# Sheet1.net
KiCad netlist of a schematic drawn in Altium Designer
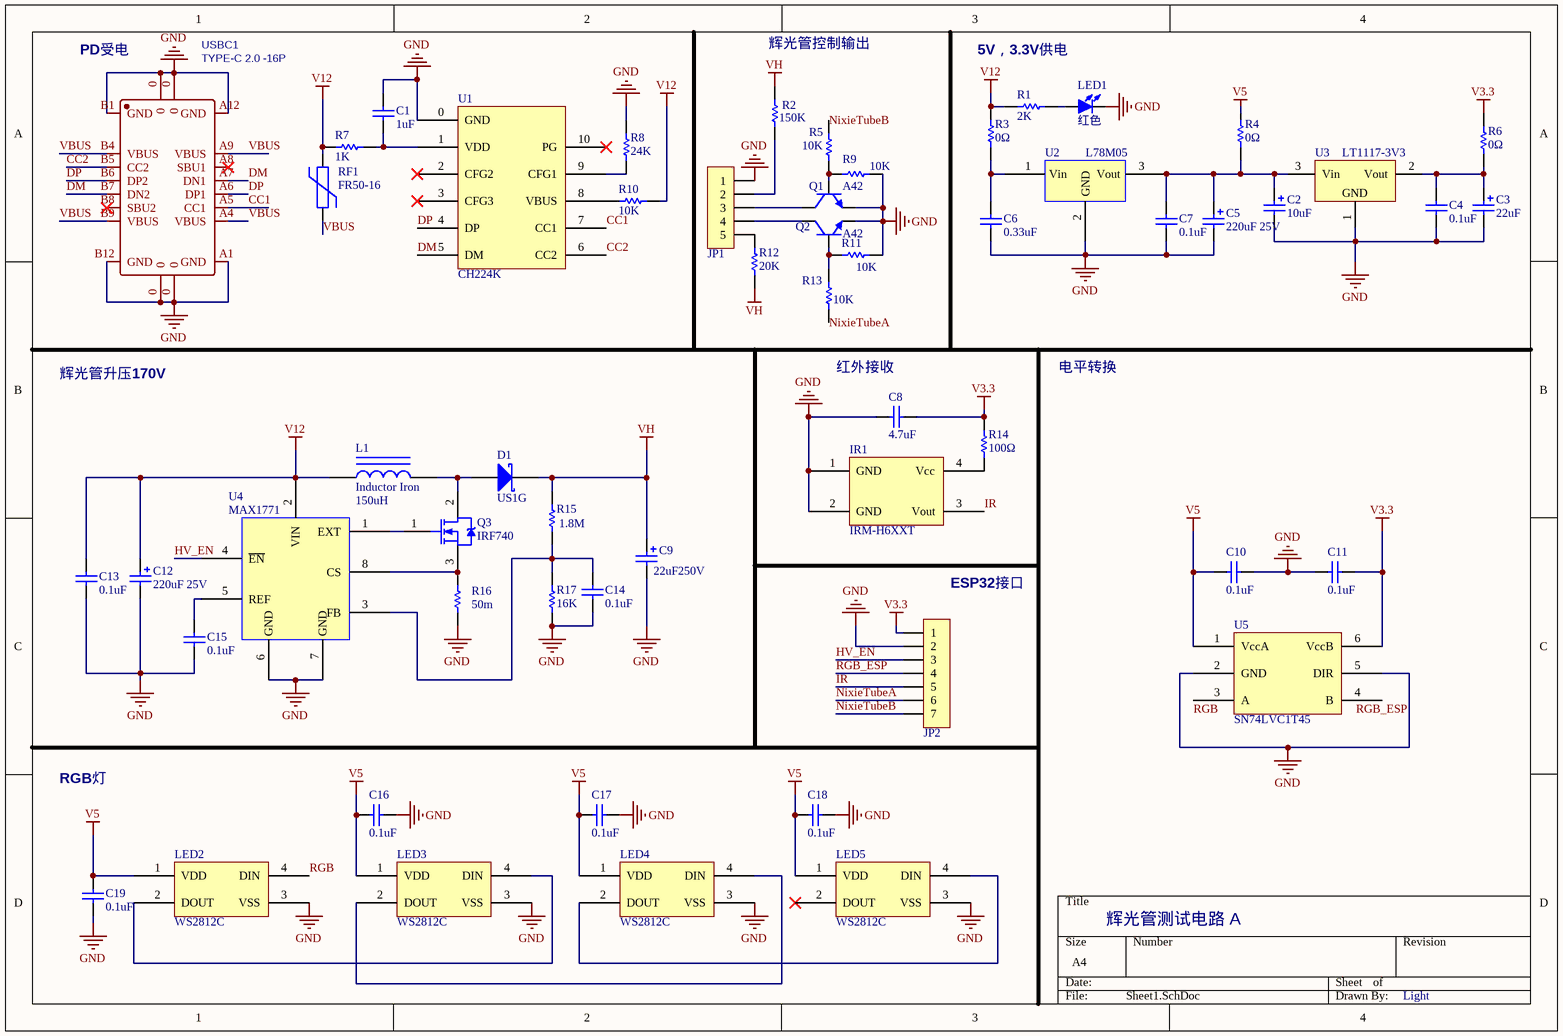
[diagram p0: Sheet1.SchDoc]

(export (version "E")
  (design (tool "Eeschema 10.0.6"))
  (components
    (comp (ref "C1")
      (value "1uF")
      (footprint "C 0805_L")
      (description "Capacitor")
      (fields (field (name "Comment") "Cap") (field (name "PUBLISHER") "Altium Limited"))
      (libsource (lib "Nixie") (part "Cap"))
    )
    (comp (ref "C2")
      (value "10uF")
      (footprint "CM B(4*5.4)")
      (description "Polarized Capacitor (Radial)")
      (fields (field (name "Comment") "Cap Pol1") (field (name "PUBLISHER") "Altium Limited"))
      (libsource (lib "Nixie") (part "Cap Pol1"))
    )
    (comp (ref "C3")
      (value "22uF")
      (footprint "CD C(6032)")
      (description "Polarized Capacitor (Radial)")
      (fields (field (name "Comment") "Cap Pol1") (field (name "PUBLISHER") "Altium Limited"))
      (libsource (lib "Nixie") (part "Cap Pol1"))
    )
    (comp (ref "C4")
      (value "0.1uF")
      (footprint "C 0805_L")
      (description "Capacitor")
      (fields (field (name "Comment") "Cap") (field (name "PUBLISHER") "Altium Limited"))
      (libsource (lib "Nixie") (part "Cap"))
    )
    (comp (ref "C5")
      (value "220uF 25V")
      (footprint "CM E(8*10.2)")
      (description "Polarized Capacitor (Radial)")
      (fields
        (field (name "VOLTAGE") "16V")
        (field (name "Comment") "Cap Pol1")
        (field (name "PUBLISHER") "Altium Limited")
      )
      (libsource (lib "Nixie") (part "Cap Pol1_2"))
    )
    (comp (ref "C6")
      (value "0.33uF")
      (footprint "C 0805_L")
      (description "Capacitor")
      (fields (field (name "Comment") "Cap") (field (name "PUBLISHER") "Altium Limited"))
      (libsource (lib "Nixie") (part "Cap"))
    )
    (comp (ref "C7")
      (value "0.1uF")
      (footprint "C 0805_L")
      (description "Capacitor")
      (fields (field (name "Comment") "Cap") (field (name "PUBLISHER") "Altium Limited"))
      (libsource (lib "Nixie") (part "Cap"))
    )
    (comp (ref "C8")
      (value "4.7uF")
      (footprint "C 0805_L")
      (description "Capacitor")
      (fields (field (name "Comment") "Cap") (field (name "PUBLISHER") "Altium Limited"))
      (libsource (lib "Nixie") (part "Cap"))
    )
    (comp (ref "C9")
      (value "22uF250V")
      (footprint "CAP 5.0*10*16-H - GD")
      (description "Polarized Capacitor (Radial)")
      (fields (field (name "Comment") "Cap Pol1") (field (name "PUBLISHER") "Altium Limited"))
      (libsource (lib "Nixie") (part "Cap Pol1_3"))
    )
    (comp (ref "C10")
      (value "0.1uF")
      (footprint "C 0805_L")
      (description "Capacitor")
      (fields (field (name "Comment") "Cap") (field (name "PUBLISHER") "Altium Limited"))
      (libsource (lib "Nixie") (part "Cap"))
    )
    (comp (ref "C11")
      (value "0.1uF")
      (footprint "C 0805_L")
      (description "Capacitor")
      (fields (field (name "Comment") "Cap") (field (name "PUBLISHER") "Altium Limited"))
      (libsource (lib "Nixie") (part "Cap"))
    )
    (comp (ref "C12")
      (value "220uF 25V")
      (footprint "CM E(8*10.2)")
      (description "Polarized Capacitor (Radial)")
      (fields
        (field (name "VOLTAGE") "16V")
        (field (name "Comment") "Cap Pol1")
        (field (name "PUBLISHER") "Altium Limited")
      )
      (libsource (lib "Nixie") (part "Cap Pol1_2"))
    )
    (comp (ref "C13")
      (value "0.1uF")
      (footprint "C 0805_L")
      (description "Capacitor")
      (fields (field (name "Comment") "Cap") (field (name "PUBLISHER") "Altium Limited"))
      (libsource (lib "Nixie") (part "Cap"))
    )
    (comp (ref "C14")
      (value "0.1uF")
      (footprint "C 0805_L")
      (description "Capacitor")
      (fields (field (name "Comment") "Cap") (field (name "PUBLISHER") "Altium Limited"))
      (libsource (lib "Nixie") (part "Cap"))
    )
    (comp (ref "C15")
      (value "0.1uF")
      (footprint "C 0805_L")
      (description "Capacitor")
      (fields (field (name "Comment") "Cap") (field (name "PUBLISHER") "Altium Limited"))
      (libsource (lib "Schlib1") (part "Cap"))
    )
    (comp (ref "C16")
      (value "0.1uF")
      (footprint "C 0805_L")
      (description "Capacitor")
      (fields (field (name "Comment") "Cap") (field (name "PUBLISHER") "Altium Limited"))
      (libsource (lib "Nixie") (part "Cap"))
    )
    (comp (ref "C17")
      (value "0.1uF")
      (footprint "C 0805_L")
      (description "Capacitor")
      (fields (field (name "Comment") "Cap") (field (name "PUBLISHER") "Altium Limited"))
      (libsource (lib "Nixie") (part "Cap"))
    )
    (comp (ref "C18")
      (value "0.1uF")
      (footprint "C 0805_L")
      (description "Capacitor")
      (fields (field (name "Comment") "Cap") (field (name "PUBLISHER") "Altium Limited"))
      (libsource (lib "Nixie") (part "Cap"))
    )
    (comp (ref "C19")
      (value "0.1uF")
      (footprint "C 0805_L")
      (description "Capacitor")
      (fields (field (name "Comment") "Cap") (field (name "PUBLISHER") "Altium Limited"))
      (libsource (lib "Nixie") (part "Cap"))
    )
    (comp (ref "D1")
      (value "US1G")
      (footprint "SMA")
      (description "Schottky Diode")
      (fields (field (name "PUBLISHER") "Altium Limited"))
      (libsource (lib "Nixie") (part "D Schottky"))
    )
    (comp (ref "IR1") (value "IRM-H6XXT") (footprint "SMD4_IR") (libsource (lib "Nixie") (part "IR")))
    (comp (ref "JP1")
      (value "HDR-1X5")
      (footprint "XH2.54-LI-5P")
      (description "5P接插件")
      (fields (field (name "版权归属") "封装库来自淘宝 ID：黄晶宝石"))
      (libsource (lib "Nixie") (part "Header 5"))
    )
    (comp (ref "JP2")
      (value "HDR-1X7")
      (footprint "HDR2.54-LI-7P")
      (description "7P接插件")
      (fields (field (name "版权归属") "封装库来自淘宝 ID：黄晶宝石"))
      (libsource (lib "Nixie") (part "Header 7"))
    )
    (comp (ref "L1")
      (value "Inductor Iron")
      (footprint "CDRH127")
      (description "Magnetic-Core Inductor")
      (fields (field (name "ALTIUM_VALUE") "150uH") (field (name "PUBLISHER") "Altium Limited"))
      (libsource (lib "Nixie") (part "Inductor Iron"))
    )
    (comp (ref "LED1")
      (value "红色")
      (footprint "LED 1206R")
      (description "贴片LED")
      (fields (field (name "版权归属") "封装库来自淘宝 ID：黄晶宝石"))
      (libsource (lib "Nixie") (part "LED-SMD"))
    )
    (comp (ref "LED2")
      (value "WS2812C")
      (footprint "WS2812")
      (description "RGB发光管")
      (libsource (lib "Nixie") (part "WS2812"))
    )
    (comp (ref "LED3")
      (value "WS2812C")
      (footprint "WS2812")
      (description "RGB发光管")
      (libsource (lib "Nixie") (part "WS2812"))
    )
    (comp (ref "LED4")
      (value "WS2812C")
      (footprint "WS2812")
      (description "RGB发光管")
      (libsource (lib "Nixie") (part "WS2812"))
    )
    (comp (ref "LED5")
      (value "WS2812C")
      (footprint "WS2812")
      (description "RGB发光管")
      (libsource (lib "Nixie") (part "WS2812"))
    )
    (comp (ref "Q1")
      (value "A42")
      (footprint "SOT23-3L")
      (description "NPN三极管")
      (fields (field (name "PUBLISHER") "Altium Limited"))
      (libsource (lib "Nixie") (part "BCP68"))
    )
    (comp (ref "Q2")
      (value "A42")
      (footprint "SOT23-3L")
      (description "NPN三极管")
      (fields (field (name "PUBLISHER") "Altium Limited"))
      (libsource (lib "Nixie") (part "BCP68"))
    )
    (comp (ref "Q3")
      (value "IRF740")
      (footprint "TO-263-2L")
      (description "N-Channel Power MOSFET")
      (fields (field (name "PUBLISHER") "Altium Limited"))
      (libsource (lib "Nixie") (part "NMOS-2"))
    )
    (comp (ref "R1")
      (value "2K")
      (footprint "R 0805_L")
      (description "Resistor")
      (fields (field (name "PUBLISHER") "Altium Limited"))
      (libsource (lib "Nixie") (part "Resistor"))
    )
    (comp (ref "R2")
      (value "150K")
      (footprint "R 0805_L")
      (description "Semiconductor Resistor")
      (fields (field (name "Comment") "Res Semi") (field (name "PUBLISHER") "Altium Limited"))
      (libsource (lib "Schlib1") (part "Res"))
    )
    (comp (ref "R3")
      (value "0Ω")
      (footprint "R 0805_L")
      (description "Resistor")
      (fields (field (name "PUBLISHER") "Altium Limited"))
      (libsource (lib "Nixie") (part "Resistor"))
    )
    (comp (ref "R4")
      (value "0Ω")
      (footprint "R 0805_L")
      (description "Resistor")
      (fields (field (name "PUBLISHER") "Altium Limited"))
      (libsource (lib "Nixie") (part "Resistor"))
    )
    (comp (ref "R5")
      (value "10K")
      (footprint "R 0805_L")
      (description "Resistor")
      (fields (field (name "PUBLISHER") "Altium Limited"))
      (libsource (lib "Nixie") (part "Resistor"))
    )
    (comp (ref "R6")
      (value "0Ω")
      (footprint "R 0805_L")
      (description "Resistor")
      (fields (field (name "PUBLISHER") "Altium Limited"))
      (libsource (lib "Nixie") (part "Resistor"))
    )
    (comp (ref "R7")
      (value "1K")
      (footprint "R 1206_L")
      (description "Resistor")
      (fields (field (name "PUBLISHER") "Altium Limited"))
      (libsource (lib "Nixie") (part "Resistor"))
    )
    (comp (ref "R8")
      (value "24K")
      (footprint "R 0805_L")
      (description "Resistor")
      (fields (field (name "PUBLISHER") "Altium Limited"))
      (libsource (lib "Nixie") (part "Resistor"))
    )
    (comp (ref "R9")
      (value "10K")
      (footprint "R 0805_L")
      (description "Resistor")
      (fields (field (name "PUBLISHER") "Altium Limited"))
      (libsource (lib "Nixie") (part "Resistor"))
    )
    (comp (ref "R10")
      (value "10K")
      (footprint "R 0805_L")
      (description "Resistor")
      (fields (field (name "PUBLISHER") "Altium Limited"))
      (libsource (lib "Nixie") (part "Resistor"))
    )
    (comp (ref "R11")
      (value "10K")
      (footprint "R 0805_L")
      (description "Resistor")
      (fields (field (name "PUBLISHER") "Altium Limited"))
      (libsource (lib "Nixie") (part "Resistor"))
    )
    (comp (ref "R12")
      (value "20K")
      (footprint "R 0805_L")
      (description "Semiconductor Resistor")
      (fields (field (name "Comment") "Res Semi") (field (name "PUBLISHER") "Altium Limited"))
      (libsource (lib "Schlib1") (part "Res"))
    )
    (comp (ref "R13")
      (value "10K")
      (footprint "R 0805_L")
      (description "Resistor")
      (fields (field (name "PUBLISHER") "Altium Limited"))
      (libsource (lib "Nixie") (part "Resistor"))
    )
    (comp (ref "R14")
      (value "100Ω")
      (footprint "R 0805_L")
      (description "Resistor")
      (fields (field (name "PUBLISHER") "Altium Limited"))
      (libsource (lib "Nixie") (part "Resistor"))
    )
    (comp (ref "R15")
      (value "1.8M")
      (footprint "R 0805_L")
      (description "Semiconductor Resistor")
      (fields (field (name "Comment") "Res Semi") (field (name "PUBLISHER") "Altium Limited"))
      (libsource (lib "Nixie") (part "Res Semi"))
    )
    (comp (ref "R16")
      (value "50m")
      (footprint "R 1206_L")
      (description "Semiconductor Resistor")
      (fields (field (name "Comment") "Res Semi") (field (name "PUBLISHER") "Altium Limited"))
      (libsource (lib "Nixie") (part "Res Semi"))
    )
    (comp (ref "R17")
      (value "16K")
      (footprint "R 0805_L")
      (description "Resistor")
      (fields (field (name "PUBLISHER") "Altium Limited"))
      (libsource (lib "Nixie") (part "Resistor"))
    )
    (comp (ref "RF1")
      (value "FR50-16")
      (footprint "FU 1206")
      (description "PPTC自恢复保险丝")
      (fields (field (name "版权归属") "封装库来自淘宝卖家 ID：黄晶宝石"))
      (libsource (lib "Nixie") (part "PPTC"))
    )
    (comp (ref "U1")
      (value "CH224K")
      (footprint "ESSOP10")
      (description "PD协议受电芯片")
      (libsource (lib "Nixie") (part "CH224K"))
    )
    (comp (ref "U2") (value "L78M05") (footprint "TO-252") (libsource (lib "Nixie") (part "L78M05")))
    (comp (ref "U3")
      (value "LT1117-3V3")
      (footprint "SOT223_L")
      (description "三端稳压芯片")
      (fields (field (name "版权归属") "源创客"))
      (libsource (lib "Nixie") (part "AMS1117"))
    )
    (comp (ref "U4") (value "MAX1771") (footprint "SOIC8") (libsource (lib "Nixie") (part "MAX1771")))
    (comp (ref "U5")
      (value "SN74LVC1T45")
      (footprint "SOT23-6L")
      (description "单路逻辑电平转换")
      (libsource (lib "Nixie") (part "SN74LVC1T45"))
    )
    (comp (ref "USBC1")
      (value "TYPE-C 2.0 -16P")
      (footprint "USB-C-SMD_TYPE-C-USB-5")
      (description "USB2.0 Type-C 母座 16Pin")
      (libsource (lib "Nixie") (part "USB2.0 Type-C 16Pin母座"))
    )
  )
  (nets
    (net (code "1") (name "/CC1") (class "Default")
      (node (ref "U1") (pin "7") (pinfunction "CC1_7") (pintype "passive"))
      (node (ref "USBC1") (pin "A5") (pinfunction "CC1_A5") (pintype "passive"))
    )
    (net (code "2") (name "/CC2") (class "Default")
      (node (ref "U1") (pin "6") (pinfunction "CC2_6") (pintype "passive"))
      (node (ref "USBC1") (pin "B5") (pinfunction "CC2_B5") (pintype "passive"))
    )
    (net (code "3") (name "/DM") (class "Default")
      (node (ref "U1") (pin "5") (pinfunction "DM_5") (pintype "passive"))
      (node (ref "USBC1") (pin "A7") (pinfunction "DN1_A7") (pintype "passive"))
      (node (ref "USBC1") (pin "B7") (pinfunction "DN2_B7") (pintype "passive"))
    )
    (net (code "4") (name "/DP") (class "Default")
      (node (ref "U1") (pin "4") (pinfunction "DP_4") (pintype "passive"))
      (node (ref "USBC1") (pin "A6") (pinfunction "DP1_A6") (pintype "passive"))
      (node (ref "USBC1") (pin "B6") (pinfunction "DP2_B6") (pintype "passive"))
    )
    (net (code "5") (name "/HV_EN") (class "Default")
      (node (ref "JP2") (pin "3") (pinfunction "3_3") (pintype "passive"))
      (node (ref "U4") (pin "4") (pinfunction "~{EN}_4") (pintype "passive"))
    )
    (net (code "6") (name "/IR") (class "Default")
      (node (ref "IR1") (pin "3") (pinfunction "Vout_3") (pintype "passive"))
      (node (ref "JP2") (pin "5") (pinfunction "5_5") (pintype "passive"))
    )
    (net (code "7") (name "/NixieTubeA") (class "Default")
      (node (ref "JP2") (pin "6") (pinfunction "6_6") (pintype "passive"))
      (node (ref "R13") (pin "2") (pinfunction "2_2") (pintype "passive"))
    )
    (net (code "8") (name "/NixieTubeB") (class "Default")
      (node (ref "JP2") (pin "7") (pinfunction "7_7") (pintype "passive"))
      (node (ref "R5") (pin "2") (pinfunction "2_2") (pintype "passive"))
    )
    (net (code "9") (name "/RGB") (class "Default")
      (node (ref "LED2") (pin "4") (pinfunction "DIN_4") (pintype "passive"))
      (node (ref "U5") (pin "3") (pinfunction "A_3") (pintype "passive"))
    )
    (net (code "10") (name "/RGB_ESP") (class "Default")
      (node (ref "JP2") (pin "4") (pinfunction "4_4") (pintype "passive"))
      (node (ref "U5") (pin "4") (pinfunction "B_4") (pintype "passive"))
    )
    (net (code "11") (name "/VBUS") (class "Default")
      (node (ref "RF1") (pin "1") (pinfunction "1_1") (pintype "passive"))
      (node (ref "USBC1") (pin "A4") (pinfunction "VBUS_A4") (pintype "passive"))
      (node (ref "USBC1") (pin "A9") (pinfunction "VBUS_A9") (pintype "passive"))
      (node (ref "USBC1") (pin "B4") (pinfunction "VBUS_B4") (pintype "passive"))
      (node (ref "USBC1") (pin "B9") (pinfunction "VBUS_B9") (pintype "passive"))
    )
    (net (code "12") (name "GND") (class "Default")
      (node (ref "C1") (pin "2") (pinfunction "2_2") (pintype "passive"))
      (node (ref "C10") (pin "1") (pinfunction "1_1") (pintype "passive"))
      (node (ref "C11") (pin "2") (pinfunction "2_2") (pintype "passive"))
      (node (ref "C12") (pin "2") (pinfunction "2_2") (pintype "passive"))
      (node (ref "C13") (pin "1") (pinfunction "1_1") (pintype "passive"))
      (node (ref "C14") (pin "1") (pinfunction "1_1") (pintype "passive"))
      (node (ref "C15") (pin "2") (pinfunction "2_2") (pintype "passive"))
      (node (ref "C16") (pin "1") (pinfunction "1_1") (pintype "passive"))
      (node (ref "C17") (pin "1") (pinfunction "1_1") (pintype "passive"))
      (node (ref "C18") (pin "1") (pinfunction "1_1") (pintype "passive"))
      (node (ref "C19") (pin "1") (pinfunction "1_1") (pintype "passive"))
      (node (ref "C2") (pin "2") (pinfunction "2_2") (pintype "passive"))
      (node (ref "C3") (pin "2") (pinfunction "2_2") (pintype "passive"))
      (node (ref "C4") (pin "1") (pinfunction "1_1") (pintype "passive"))
      (node (ref "C5") (pin "2") (pinfunction "2_2") (pintype "passive"))
      (node (ref "C6") (pin "1") (pinfunction "1_1") (pintype "passive"))
      (node (ref "C7") (pin "1") (pinfunction "1_1") (pintype "passive"))
      (node (ref "C8") (pin "2") (pinfunction "2_2") (pintype "passive"))
      (node (ref "C9") (pin "2") (pinfunction "2_2") (pintype "passive"))
      (node (ref "IR1") (pin "1") (pinfunction "GND_1") (pintype "passive"))
      (node (ref "IR1") (pin "2") (pinfunction "GND_2") (pintype "passive"))
      (node (ref "JP1") (pin "1") (pinfunction "1_1") (pintype "passive"))
      (node (ref "JP2") (pin "2") (pinfunction "2_2") (pintype "passive"))
      (node (ref "LED1") (pin "2") (pinfunction "K_2") (pintype "passive"))
      (node (ref "LED2") (pin "3") (pinfunction "VSS_3") (pintype "passive"))
      (node (ref "LED3") (pin "3") (pinfunction "VSS_3") (pintype "passive"))
      (node (ref "LED4") (pin "3") (pinfunction "VSS_3") (pintype "passive"))
      (node (ref "LED5") (pin "3") (pinfunction "VSS_3") (pintype "passive"))
      (node (ref "Q1") (pin "2") (pinfunction "E_2") (pintype "passive"))
      (node (ref "Q2") (pin "2") (pinfunction "E_2") (pintype "passive"))
      (node (ref "R11") (pin "2") (pinfunction "2_2") (pintype "passive"))
      (node (ref "R16") (pin "2") (pinfunction "2_2") (pintype "passive"))
      (node (ref "R17") (pin "1") (pinfunction "1_1") (pintype "passive"))
      (node (ref "R8") (pin "1") (pinfunction "1_1") (pintype "passive"))
      (node (ref "R9") (pin "2") (pinfunction "2_2") (pintype "passive"))
      (node (ref "U1") (pin "0") (pinfunction "GND_0") (pintype "passive"))
      (node (ref "U2") (pin "2") (pinfunction "GND_2") (pintype "passive"))
      (node (ref "U3") (pin "1") (pinfunction "GND_1") (pintype "passive"))
      (node (ref "U4") (pin "6") (pinfunction "GND_6") (pintype "passive"))
      (node (ref "U4") (pin "7") (pinfunction "GND_7") (pintype "passive"))
      (node (ref "U5") (pin "2") (pinfunction "GND_2") (pintype "passive"))
      (node (ref "U5") (pin "5") (pinfunction "DIR_5") (pintype "passive"))
      (node (ref "USBC1") (pin "0") (pinfunction "0_0") (pintype "passive"))
      (node (ref "USBC1") (pin "A1") (pinfunction "GND_A1") (pintype "passive"))
      (node (ref "USBC1") (pin "A12") (pinfunction "GND_A12") (pintype "passive"))
      (node (ref "USBC1") (pin "B1") (pinfunction "GND_B1") (pintype "passive"))
      (node (ref "USBC1") (pin "B12") (pinfunction "GND_B12") (pintype "passive"))
    )
    (net (code "13") (name "Net-(D1-A)") (class "Default")
      (node (ref "D1") (pin "1") (pinfunction "A_1") (pintype "passive"))
      (node (ref "L1") (pin "2") (pinfunction "2_2") (pintype "passive"))
      (node (ref "Q3") (pin "2") (pinfunction "D_2") (pintype "passive"))
    )
    (net (code "14") (name "Net-(IR1-Vcc)") (class "Default")
      (node (ref "IR1") (pin "4") (pinfunction "Vcc_4") (pintype "passive"))
      (node (ref "R14") (pin "1") (pinfunction "1_1") (pintype "passive"))
    )
    (net (code "15") (name "Net-(JP1-Pad2)") (class "Default")
      (node (ref "JP1") (pin "2") (pinfunction "2_2") (pintype "passive"))
      (node (ref "R2") (pin "1") (pinfunction "1_1") (pintype "passive"))
    )
    (net (code "16") (name "Net-(JP1-Pad5)") (class "Default")
      (node (ref "JP1") (pin "5") (pinfunction "5_5") (pintype "passive"))
      (node (ref "R12") (pin "2") (pinfunction "2_2") (pintype "passive"))
    )
    (net (code "17") (name "Net-(LED1-A)") (class "Default")
      (node (ref "LED1") (pin "1") (pinfunction "A_1") (pintype "passive"))
      (node (ref "R1") (pin "1") (pinfunction "1_1") (pintype "passive"))
    )
    (net (code "18") (name "Net-(LED2-DOUT)") (class "Default")
      (node (ref "LED2") (pin "2") (pinfunction "DOUT_2") (pintype "passive"))
      (node (ref "LED3") (pin "4") (pinfunction "DIN_4") (pintype "passive"))
    )
    (net (code "19") (name "Net-(LED3-DOUT)") (class "Default")
      (node (ref "LED3") (pin "2") (pinfunction "DOUT_2") (pintype "passive"))
      (node (ref "LED4") (pin "4") (pinfunction "DIN_4") (pintype "passive"))
    )
    (net (code "20") (name "Net-(LED4-DOUT)") (class "Default")
      (node (ref "LED4") (pin "2") (pinfunction "DOUT_2") (pintype "passive"))
      (node (ref "LED5") (pin "4") (pinfunction "DIN_4") (pintype "passive"))
    )
    (net (code "21") (name "Net-(Q1-B)") (class "Default")
      (node (ref "Q1") (pin "1") (pinfunction "B_1") (pintype "passive"))
      (node (ref "R5") (pin "1") (pinfunction "1_1") (pintype "passive"))
      (node (ref "R9") (pin "1") (pinfunction "1_1") (pintype "passive"))
    )
    (net (code "22") (name "Net-(Q1-C)") (class "Default")
      (node (ref "JP1") (pin "3") (pinfunction "3_3") (pintype "passive"))
      (node (ref "Q1") (pin "3") (pinfunction "C_3") (pintype "passive"))
    )
    (net (code "23") (name "Net-(Q2-B)") (class "Default")
      (node (ref "Q2") (pin "1") (pinfunction "B_1") (pintype "passive"))
      (node (ref "R11") (pin "1") (pinfunction "1_1") (pintype "passive"))
      (node (ref "R13") (pin "1") (pinfunction "1_1") (pintype "passive"))
    )
    (net (code "24") (name "Net-(Q2-C)") (class "Default")
      (node (ref "JP1") (pin "4") (pinfunction "4_4") (pintype "passive"))
      (node (ref "Q2") (pin "3") (pinfunction "C_3") (pintype "passive"))
    )
    (net (code "25") (name "Net-(Q3-G)") (class "Default")
      (node (ref "Q3") (pin "1") (pinfunction "G_1") (pintype "passive"))
      (node (ref "U4") (pin "1") (pinfunction "EXT_1") (pintype "passive"))
    )
    (net (code "26") (name "Net-(Q3-S)") (class "Default")
      (node (ref "Q3") (pin "3") (pinfunction "S_3") (pintype "passive"))
      (node (ref "R16") (pin "1") (pinfunction "1_1") (pintype "passive"))
      (node (ref "U4") (pin "8") (pinfunction "CS_8") (pintype "passive"))
    )
    (net (code "27") (name "Net-(U1-CFG1)") (class "Default")
      (node (ref "R8") (pin "2") (pinfunction "2_2") (pintype "passive"))
      (node (ref "U1") (pin "9") (pinfunction "CFG1_9") (pintype "passive"))
    )
    (net (code "28") (name "Net-(U1-VBUS)") (class "Default")
      (node (ref "R10") (pin "2") (pinfunction "2_2") (pintype "passive"))
      (node (ref "U1") (pin "8") (pinfunction "VBUS_8") (pintype "passive"))
    )
    (net (code "29") (name "Net-(U1-VDD)") (class "Default")
      (node (ref "C1") (pin "1") (pinfunction "1_1") (pintype "passive"))
      (node (ref "R7") (pin "1") (pinfunction "1_1") (pintype "passive"))
      (node (ref "U1") (pin "1") (pinfunction "VDD_1") (pintype "passive"))
    )
    (net (code "30") (name "Net-(U2-Vin)") (class "Default")
      (node (ref "C6") (pin "2") (pinfunction "2_2") (pintype "passive"))
      (node (ref "R3") (pin "1") (pinfunction "1_1") (pintype "passive"))
      (node (ref "U2") (pin "1") (pinfunction "Vin_1") (pintype "passive"))
    )
    (net (code "31") (name "Net-(U2-Vout)") (class "Default")
      (node (ref "C2") (pin "1") (pinfunction "1_1") (pintype "passive"))
      (node (ref "C5") (pin "1") (pinfunction "1_1") (pintype "passive"))
      (node (ref "C7") (pin "2") (pinfunction "2_2") (pintype "passive"))
      (node (ref "R4") (pin "1") (pinfunction "1_1") (pintype "passive"))
      (node (ref "U2") (pin "3") (pinfunction "Vout_3") (pintype "passive"))
      (node (ref "U3") (pin "3") (pinfunction "Vin_3") (pintype "passive"))
    )
    (net (code "32") (name "Net-(U3-Vout)") (class "Default")
      (node (ref "C3") (pin "1") (pinfunction "1_1") (pintype "passive"))
      (node (ref "C4") (pin "2") (pinfunction "2_2") (pintype "passive"))
      (node (ref "R6") (pin "1") (pinfunction "1_1") (pintype "passive"))
      (node (ref "U3") (pin "2") (pinfunction "Vout_2") (pintype "passive"))
    )
    (net (code "33") (name "Net-(U4-FB)") (class "Default")
      (node (ref "C14") (pin "2") (pinfunction "2_2") (pintype "passive"))
      (node (ref "R15") (pin "2") (pinfunction "2_2") (pintype "passive"))
      (node (ref "R17") (pin "2") (pinfunction "2_2") (pintype "passive"))
      (node (ref "U4") (pin "3") (pinfunction "FB_3") (pintype "passive"))
    )
    (net (code "34") (name "Net-(U4-REF)") (class "Default")
      (node (ref "C15") (pin "1") (pinfunction "1_1") (pintype "passive"))
      (node (ref "U4") (pin "5") (pinfunction "REF_5") (pintype "passive"))
    )
    (net (code "35") (name "V3.3") (class "Default")
      (node (ref "C11") (pin "1") (pinfunction "1_1") (pintype "passive"))
      (node (ref "C8") (pin "1") (pinfunction "1_1") (pintype "passive"))
      (node (ref "JP2") (pin "1") (pinfunction "1_1") (pintype "passive"))
      (node (ref "R14") (pin "2") (pinfunction "2_2") (pintype "passive"))
      (node (ref "R6") (pin "2") (pinfunction "2_2") (pintype "passive"))
      (node (ref "U5") (pin "6") (pinfunction "VccB_6") (pintype "passive"))
    )
    (net (code "36") (name "V5") (class "Default")
      (node (ref "C10") (pin "2") (pinfunction "2_2") (pintype "passive"))
      (node (ref "C16") (pin "2") (pinfunction "2_2") (pintype "passive"))
      (node (ref "C17") (pin "2") (pinfunction "2_2") (pintype "passive"))
      (node (ref "C18") (pin "2") (pinfunction "2_2") (pintype "passive"))
      (node (ref "C19") (pin "2") (pinfunction "2_2") (pintype "passive"))
      (node (ref "LED2") (pin "1") (pinfunction "VDD_1") (pintype "passive"))
      (node (ref "LED3") (pin "1") (pinfunction "VDD_1") (pintype "passive"))
      (node (ref "LED4") (pin "1") (pinfunction "VDD_1") (pintype "passive"))
      (node (ref "LED5") (pin "1") (pinfunction "VDD_1") (pintype "passive"))
      (node (ref "R4") (pin "2") (pinfunction "2_2") (pintype "passive"))
      (node (ref "U5") (pin "1") (pinfunction "VccA_1") (pintype "passive"))
    )
    (net (code "37") (name "V12") (class "Default")
      (node (ref "C12") (pin "1") (pinfunction "1_1") (pintype "passive"))
      (node (ref "C13") (pin "2") (pinfunction "2_2") (pintype "passive"))
      (node (ref "L1") (pin "1") (pinfunction "1_1") (pintype "passive"))
      (node (ref "R1") (pin "2") (pinfunction "2_2") (pintype "passive"))
      (node (ref "R10") (pin "1") (pinfunction "1_1") (pintype "passive"))
      (node (ref "R3") (pin "2") (pinfunction "2_2") (pintype "passive"))
      (node (ref "R7") (pin "2") (pinfunction "2_2") (pintype "passive"))
      (node (ref "RF1") (pin "2") (pinfunction "2_2") (pintype "passive"))
      (node (ref "U4") (pin "2") (pinfunction "VIN_2") (pintype "passive"))
    )
    (net (code "38") (name "VH") (class "Default")
      (node (ref "C9") (pin "1") (pinfunction "1_1") (pintype "passive"))
      (node (ref "D1") (pin "2") (pinfunction "K_2") (pintype "passive"))
      (node (ref "R12") (pin "1") (pinfunction "1_1") (pintype "passive"))
      (node (ref "R15") (pin "1") (pinfunction "1_1") (pintype "passive"))
      (node (ref "R2") (pin "2") (pinfunction "2_2") (pintype "passive"))
    )
    (net (code "39") (name "unconnected-(LED5-DOUT-Pad2)") (class "Default")
      (node (ref "LED5") (pin "2") (pinfunction "DOUT_2") (pintype "passive+no_connect"))
    )
    (net (code "40") (name "unconnected-(U1-CFG2-Pad2)") (class "Default")
      (node (ref "U1") (pin "2") (pinfunction "CFG2_2") (pintype "passive+no_connect"))
    )
    (net (code "41") (name "unconnected-(U1-CFG3-Pad3)") (class "Default")
      (node (ref "U1") (pin "3") (pinfunction "CFG3_3") (pintype "passive+no_connect"))
    )
    (net (code "42") (name "unconnected-(U1-PG-Pad10)") (class "Default")
      (node (ref "U1") (pin "10") (pinfunction "PG_10") (pintype "passive+no_connect"))
    )
    (net (code "43") (name "unconnected-(USBC1-SBU1-PadA8)") (class "Default")
      (node (ref "USBC1") (pin "A8") (pinfunction "SBU1_A8") (pintype "passive+no_connect"))
    )
    (net (code "44") (name "unconnected-(USBC1-SBU2-PadB8)") (class "Default")
      (node (ref "USBC1") (pin "B8") (pinfunction "SBU2_B8") (pintype "passive+no_connect"))
    )
  )
)
